# SH5_-_ARMCONTROLS.net
KiCad netlist of a schematic drawn in Altium Designer
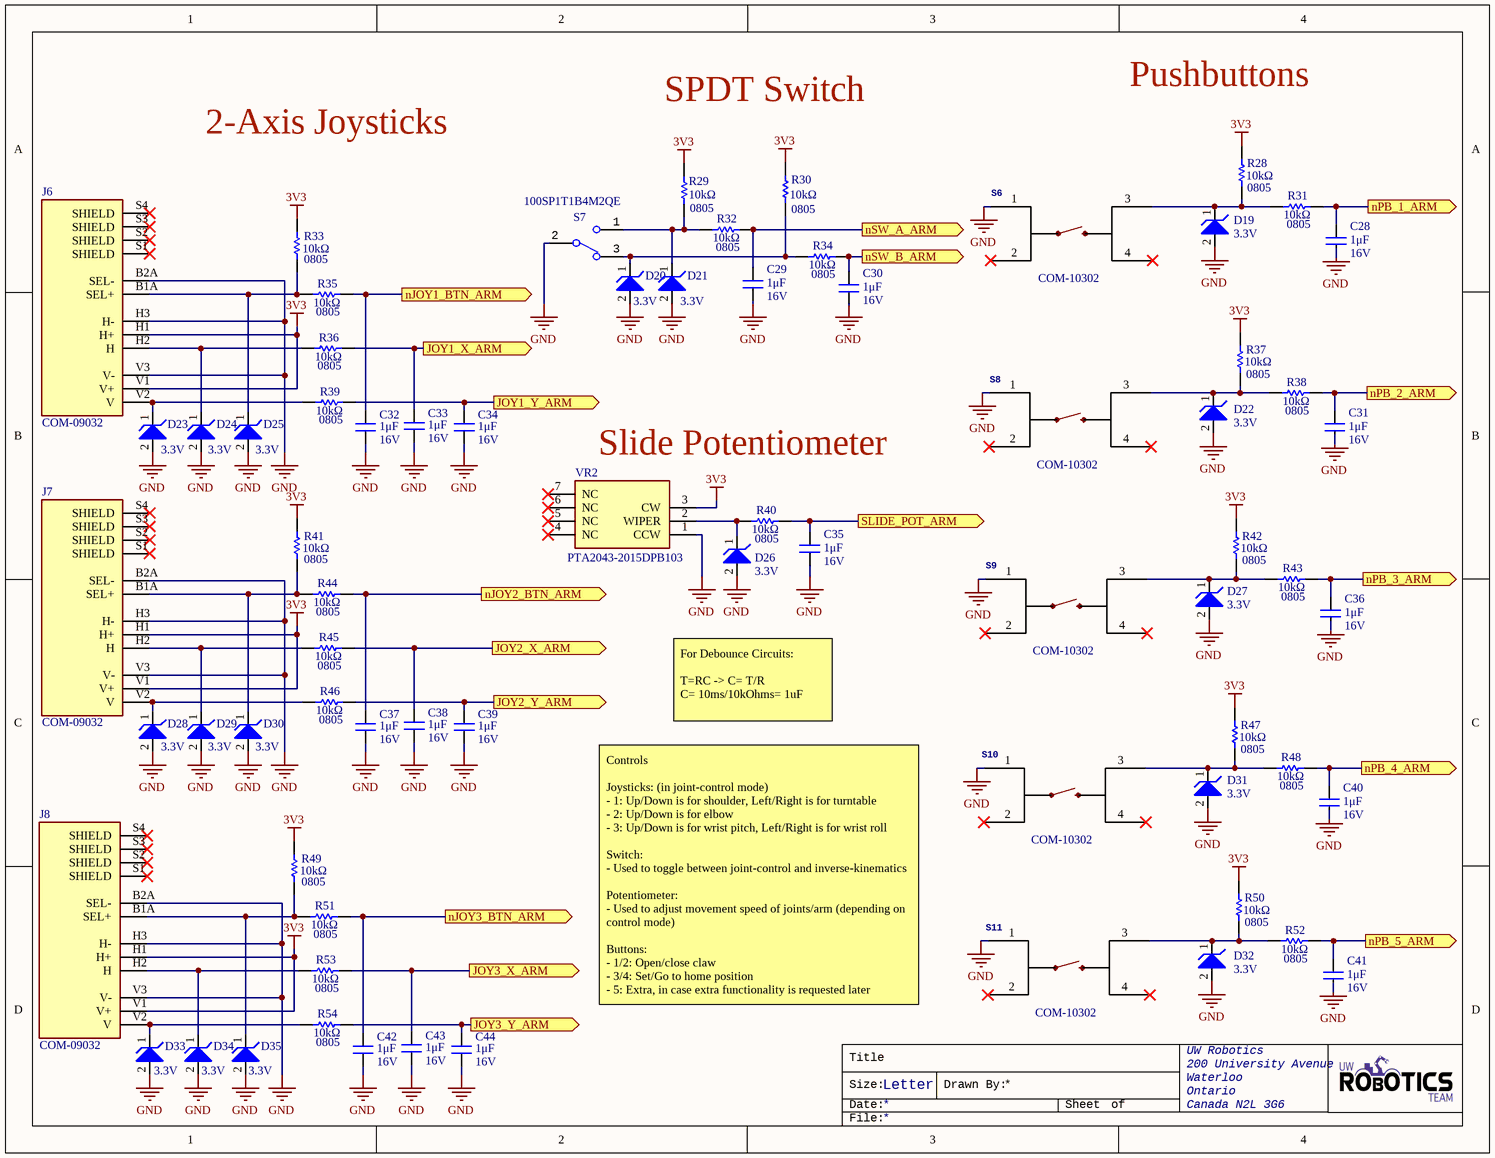
[diagram p0: SH5 - ARMCONTROLS.SchDoc]

(export (version "E")
  (design (tool "Eeschema 10.0.6"))
  (components
    (comp (ref "C28")
      (value "1μF")
      (footprint "CAP2012")
      (description "CAP CER 1UF 16V X7R 0805")
      (fields
        (field (name "TOLERANCE") "10%")
        (field (name "VOLTAGE RATING") "16V")
        (field (name "Comment") "CAP_1uF_16V_0805")
      )
      (libsource (lib "UWRT_Schematic_Library_2020") (part "CAP_1uF_16V_0805"))
    )
    (comp (ref "C29")
      (value "1μF")
      (footprint "CAP2012")
      (description "CAP CER 1UF 16V X7R 0805")
      (fields
        (field (name "TOLERANCE") "10%")
        (field (name "VOLTAGE RATING") "16V")
        (field (name "Comment") "CAP_1uF_16V_0805")
      )
      (libsource (lib "UWRT_Schematic_Library_2020") (part "CAP_1uF_16V_0805"))
    )
    (comp (ref "C30")
      (value "1μF")
      (footprint "CAP2012")
      (description "CAP CER 1UF 16V X7R 0805")
      (fields
        (field (name "TOLERANCE") "10%")
        (field (name "VOLTAGE RATING") "16V")
        (field (name "Comment") "CAP_1uF_16V_0805")
      )
      (libsource (lib "UWRT_Schematic_Library_2020") (part "CAP_1uF_16V_0805"))
    )
    (comp (ref "C31")
      (value "1μF")
      (footprint "CAP2012")
      (description "CAP CER 1UF 16V X7R 0805")
      (fields
        (field (name "TOLERANCE") "10%")
        (field (name "VOLTAGE RATING") "16V")
        (field (name "Comment") "CAP_1uF_16V_0805")
      )
      (libsource (lib "UWRT_Schematic_Library_2020") (part "CAP_1uF_16V_0805"))
    )
    (comp (ref "C32")
      (value "1μF")
      (footprint "CAP2012")
      (description "CAP CER 1UF 16V X7R 0805")
      (fields
        (field (name "TOLERANCE") "10%")
        (field (name "VOLTAGE RATING") "16V")
        (field (name "Comment") "CAP_1uF_16V_0805")
      )
      (libsource (lib "UWRT_Schematic_Library_2020") (part "CAP_1uF_16V_0805"))
    )
    (comp (ref "C33")
      (value "1μF")
      (footprint "CAP2012")
      (description "CAP CER 1UF 16V X7R 0805")
      (fields
        (field (name "TOLERANCE") "10%")
        (field (name "VOLTAGE RATING") "16V")
        (field (name "Comment") "CAP_1uF_16V_0805")
      )
      (libsource (lib "UWRT_Schematic_Library_2020") (part "CAP_1uF_16V_0805"))
    )
    (comp (ref "C34")
      (value "1μF")
      (footprint "CAP2012")
      (description "CAP CER 1UF 16V X7R 0805")
      (fields
        (field (name "TOLERANCE") "10%")
        (field (name "VOLTAGE RATING") "16V")
        (field (name "Comment") "CAP_1uF_16V_0805")
      )
      (libsource (lib "UWRT_Schematic_Library_2020") (part "CAP_1uF_16V_0805"))
    )
    (comp (ref "C35")
      (value "1μF")
      (footprint "CAP2012")
      (description "CAP CER 1UF 16V X7R 0805")
      (fields
        (field (name "TOLERANCE") "10%")
        (field (name "VOLTAGE RATING") "16V")
        (field (name "Comment") "CAP_1uF_16V_0805")
      )
      (libsource (lib "UWRT_Schematic_Library_2020") (part "CAP_1uF_16V_0805"))
    )
    (comp (ref "C36")
      (value "1μF")
      (footprint "CAP2012")
      (description "CAP CER 1UF 16V X7R 0805")
      (fields
        (field (name "TOLERANCE") "10%")
        (field (name "VOLTAGE RATING") "16V")
        (field (name "Comment") "CAP_1uF_16V_0805")
      )
      (libsource (lib "UWRT_Schematic_Library_2020") (part "CAP_1uF_16V_0805"))
    )
    (comp (ref "C37")
      (value "1μF")
      (footprint "CAP2012")
      (description "CAP CER 1UF 16V X7R 0805")
      (fields
        (field (name "TOLERANCE") "10%")
        (field (name "VOLTAGE RATING") "16V")
        (field (name "Comment") "CAP_1uF_16V_0805")
      )
      (libsource (lib "UWRT_Schematic_Library_2020") (part "CAP_1uF_16V_0805"))
    )
    (comp (ref "C38")
      (value "1μF")
      (footprint "CAP2012")
      (description "CAP CER 1UF 16V X7R 0805")
      (fields
        (field (name "TOLERANCE") "10%")
        (field (name "VOLTAGE RATING") "16V")
        (field (name "Comment") "CAP_1uF_16V_0805")
      )
      (libsource (lib "UWRT_Schematic_Library_2020") (part "CAP_1uF_16V_0805"))
    )
    (comp (ref "C39")
      (value "1μF")
      (footprint "CAP2012")
      (description "CAP CER 1UF 16V X7R 0805")
      (fields
        (field (name "TOLERANCE") "10%")
        (field (name "VOLTAGE RATING") "16V")
        (field (name "Comment") "CAP_1uF_16V_0805")
      )
      (libsource (lib "UWRT_Schematic_Library_2020") (part "CAP_1uF_16V_0805"))
    )
    (comp (ref "C40")
      (value "1μF")
      (footprint "CAP2012")
      (description "CAP CER 1UF 16V X7R 0805")
      (fields
        (field (name "TOLERANCE") "10%")
        (field (name "VOLTAGE RATING") "16V")
        (field (name "Comment") "CAP_1uF_16V_0805")
      )
      (libsource (lib "UWRT_Schematic_Library_2020") (part "CAP_1uF_16V_0805"))
    )
    (comp (ref "C41")
      (value "1μF")
      (footprint "CAP2012")
      (description "CAP CER 1UF 16V X7R 0805")
      (fields
        (field (name "TOLERANCE") "10%")
        (field (name "VOLTAGE RATING") "16V")
        (field (name "Comment") "CAP_1uF_16V_0805")
      )
      (libsource (lib "UWRT_Schematic_Library_2020") (part "CAP_1uF_16V_0805"))
    )
    (comp (ref "C42")
      (value "1μF")
      (footprint "CAP2012")
      (description "CAP CER 1UF 16V X7R 0805")
      (fields
        (field (name "TOLERANCE") "10%")
        (field (name "VOLTAGE RATING") "16V")
        (field (name "Comment") "CAP_1uF_16V_0805")
      )
      (libsource (lib "UWRT_Schematic_Library_2020") (part "CAP_1uF_16V_0805"))
    )
    (comp (ref "C43")
      (value "1μF")
      (footprint "CAP2012")
      (description "CAP CER 1UF 16V X7R 0805")
      (fields
        (field (name "TOLERANCE") "10%")
        (field (name "VOLTAGE RATING") "16V")
        (field (name "Comment") "CAP_1uF_16V_0805")
      )
      (libsource (lib "UWRT_Schematic_Library_2020") (part "CAP_1uF_16V_0805"))
    )
    (comp (ref "C44")
      (value "1μF")
      (footprint "CAP2012")
      (description "CAP CER 1UF 16V X7R 0805")
      (fields
        (field (name "TOLERANCE") "10%")
        (field (name "VOLTAGE RATING") "16V")
        (field (name "Comment") "CAP_1uF_16V_0805")
      )
      (libsource (lib "UWRT_Schematic_Library_2020") (part "CAP_1uF_16V_0805"))
    )
    (comp (ref "D19")
      (value "TVS_DIODE_UNIDIR_3.3V")
      (footprint "SOD523")
      (description "TVS DIODE 3.3V 14.1V SOD523. Used to protect each connector input line going into the MCU.")
      (fields (field (name "REVERSE STANDOFF VOLTAGE") "3.3V"))
      (libsource (lib "UWRT_Schematic_Library_2020") (part "TVS_DIODE_UNIDIR_3.3V"))
    )
    (comp (ref "D20")
      (value "TVS_DIODE_UNIDIR_3.3V")
      (footprint "SOD523")
      (description "TVS DIODE 3.3V 14.1V SOD523. Used to protect each connector input line going into the MCU.")
      (fields (field (name "REVERSE STANDOFF VOLTAGE") "3.3V"))
      (libsource (lib "UWRT_Schematic_Library_2020") (part "TVS_DIODE_UNIDIR_3.3V"))
    )
    (comp (ref "D21")
      (value "TVS_DIODE_UNIDIR_3.3V")
      (footprint "SOD523")
      (description "TVS DIODE 3.3V 14.1V SOD523. Used to protect each connector input line going into the MCU.")
      (fields (field (name "REVERSE STANDOFF VOLTAGE") "3.3V"))
      (libsource (lib "UWRT_Schematic_Library_2020") (part "TVS_DIODE_UNIDIR_3.3V"))
    )
    (comp (ref "D22")
      (value "TVS_DIODE_UNIDIR_3.3V")
      (footprint "SOD523")
      (description "TVS DIODE 3.3V 14.1V SOD523. Used to protect each connector input line going into the MCU.")
      (fields (field (name "REVERSE STANDOFF VOLTAGE") "3.3V"))
      (libsource (lib "UWRT_Schematic_Library_2020") (part "TVS_DIODE_UNIDIR_3.3V"))
    )
    (comp (ref "D23")
      (value "TVS_DIODE_UNIDIR_3.3V")
      (footprint "SOD523")
      (description "TVS DIODE 3.3V 14.1V SOD523. Used to protect each connector input line going into the MCU.")
      (fields (field (name "REVERSE STANDOFF VOLTAGE") "3.3V"))
      (libsource (lib "UWRT_Schematic_Library_2020") (part "TVS_DIODE_UNIDIR_3.3V"))
    )
    (comp (ref "D24")
      (value "TVS_DIODE_UNIDIR_3.3V")
      (footprint "SOD523")
      (description "TVS DIODE 3.3V 14.1V SOD523. Used to protect each connector input line going into the MCU.")
      (fields (field (name "REVERSE STANDOFF VOLTAGE") "3.3V"))
      (libsource (lib "UWRT_Schematic_Library_2020") (part "TVS_DIODE_UNIDIR_3.3V"))
    )
    (comp (ref "D25")
      (value "TVS_DIODE_UNIDIR_3.3V")
      (footprint "SOD523")
      (description "TVS DIODE 3.3V 14.1V SOD523. Used to protect each connector input line going into the MCU.")
      (fields (field (name "REVERSE STANDOFF VOLTAGE") "3.3V"))
      (libsource (lib "UWRT_Schematic_Library_2020") (part "TVS_DIODE_UNIDIR_3.3V"))
    )
    (comp (ref "D26")
      (value "TVS_DIODE_UNIDIR_3.3V")
      (footprint "SOD523")
      (description "TVS DIODE 3.3V 14.1V SOD523. Used to protect each connector input line going into the MCU.")
      (fields (field (name "REVERSE STANDOFF VOLTAGE") "3.3V"))
      (libsource (lib "UWRT_Schematic_Library_2020") (part "TVS_DIODE_UNIDIR_3.3V"))
    )
    (comp (ref "D27")
      (value "TVS_DIODE_UNIDIR_3.3V")
      (footprint "SOD523")
      (description "TVS DIODE 3.3V 14.1V SOD523. Used to protect each connector input line going into the MCU.")
      (fields (field (name "REVERSE STANDOFF VOLTAGE") "3.3V"))
      (libsource (lib "UWRT_Schematic_Library_2020") (part "TVS_DIODE_UNIDIR_3.3V"))
    )
    (comp (ref "D28")
      (value "TVS_DIODE_UNIDIR_3.3V")
      (footprint "SOD523")
      (description "TVS DIODE 3.3V 14.1V SOD523. Used to protect each connector input line going into the MCU.")
      (fields (field (name "REVERSE STANDOFF VOLTAGE") "3.3V"))
      (libsource (lib "UWRT_Schematic_Library_2020") (part "TVS_DIODE_UNIDIR_3.3V"))
    )
    (comp (ref "D29")
      (value "TVS_DIODE_UNIDIR_3.3V")
      (footprint "SOD523")
      (description "TVS DIODE 3.3V 14.1V SOD523. Used to protect each connector input line going into the MCU.")
      (fields (field (name "REVERSE STANDOFF VOLTAGE") "3.3V"))
      (libsource (lib "UWRT_Schematic_Library_2020") (part "TVS_DIODE_UNIDIR_3.3V"))
    )
    (comp (ref "D30")
      (value "TVS_DIODE_UNIDIR_3.3V")
      (footprint "SOD523")
      (description "TVS DIODE 3.3V 14.1V SOD523. Used to protect each connector input line going into the MCU.")
      (fields (field (name "REVERSE STANDOFF VOLTAGE") "3.3V"))
      (libsource (lib "UWRT_Schematic_Library_2020") (part "TVS_DIODE_UNIDIR_3.3V"))
    )
    (comp (ref "D31")
      (value "TVS_DIODE_UNIDIR_3.3V")
      (footprint "SOD523")
      (description "TVS DIODE 3.3V 14.1V SOD523. Used to protect each connector input line going into the MCU.")
      (fields (field (name "REVERSE STANDOFF VOLTAGE") "3.3V"))
      (libsource (lib "UWRT_Schematic_Library_2020") (part "TVS_DIODE_UNIDIR_3.3V"))
    )
    (comp (ref "D32")
      (value "TVS_DIODE_UNIDIR_3.3V")
      (footprint "SOD523")
      (description "TVS DIODE 3.3V 14.1V SOD523. Used to protect each connector input line going into the MCU.")
      (fields (field (name "REVERSE STANDOFF VOLTAGE") "3.3V"))
      (libsource (lib "UWRT_Schematic_Library_2020") (part "TVS_DIODE_UNIDIR_3.3V"))
    )
    (comp (ref "D33")
      (value "TVS_DIODE_UNIDIR_3.3V")
      (footprint "SOD523")
      (description "TVS DIODE 3.3V 14.1V SOD523. Used to protect each connector input line going into the MCU.")
      (fields (field (name "REVERSE STANDOFF VOLTAGE") "3.3V"))
      (libsource (lib "UWRT_Schematic_Library_2020") (part "TVS_DIODE_UNIDIR_3.3V"))
    )
    (comp (ref "D34")
      (value "TVS_DIODE_UNIDIR_3.3V")
      (footprint "SOD523")
      (description "TVS DIODE 3.3V 14.1V SOD523. Used to protect each connector input line going into the MCU.")
      (fields (field (name "REVERSE STANDOFF VOLTAGE") "3.3V"))
      (libsource (lib "UWRT_Schematic_Library_2020") (part "TVS_DIODE_UNIDIR_3.3V"))
    )
    (comp (ref "D35")
      (value "TVS_DIODE_UNIDIR_3.3V")
      (footprint "SOD523")
      (description "TVS DIODE 3.3V 14.1V SOD523. Used to protect each connector input line going into the MCU.")
      (fields (field (name "REVERSE STANDOFF VOLTAGE") "3.3V"))
      (libsource (lib "UWRT_Schematic_Library_2020") (part "TVS_DIODE_UNIDIR_3.3V"))
    )
    (comp (ref "J6")
      (value "2_AXIS_JOYSTICK")
      (footprint "2_AXIS_JOYSTICK")
      (description "JOYSTICK 10K OHM 2 AXIS TH")
      (fields (field (name "MANUFACTURER PART NUMBER 1") "COM-09032"))
      (libsource (lib "UWRT_Schematic_Library_2020") (part "2_AXIS_JOYSTICK"))
    )
    (comp (ref "J7")
      (value "2_AXIS_JOYSTICK")
      (footprint "2_AXIS_JOYSTICK")
      (description "JOYSTICK 10K OHM 2 AXIS TH")
      (fields (field (name "MANUFACTURER PART NUMBER 1") "COM-09032"))
      (libsource (lib "UWRT_Schematic_Library_2020") (part "2_AXIS_JOYSTICK"))
    )
    (comp (ref "J8")
      (value "2_AXIS_JOYSTICK")
      (footprint "2_AXIS_JOYSTICK")
      (description "JOYSTICK 10K OHM 2 AXIS TH")
      (fields (field (name "MANUFACTURER PART NUMBER 1") "COM-09032"))
      (libsource (lib "UWRT_Schematic_Library_2020") (part "2_AXIS_JOYSTICK"))
    )
    (comp (ref "R28")
      (value "10kΩ")
      (footprint "RESC0805")
      (description "RES 10K OHM 5% 1/8W 0805")
      (fields (field (name "CASE CODE (IMPERIAL)") "0805") (field (name "Comment") "RES_10kΩ_0805_5%"))
      (libsource (lib "UWRT_Schematic_Library_2020") (part "RES_10kΩ_0805_5%"))
    )
    (comp (ref "R29")
      (value "10kΩ")
      (footprint "RESC0805")
      (description "RES 10K OHM 5% 1/8W 0805")
      (fields (field (name "CASE CODE (IMPERIAL)") "0805") (field (name "Comment") "RES_10kΩ_0805_5%"))
      (libsource (lib "UWRT_Schematic_Library_2020") (part "RES_10kΩ_0805_5%"))
    )
    (comp (ref "R30")
      (value "10kΩ")
      (footprint "RESC0805")
      (description "RES 10K OHM 5% 1/8W 0805")
      (fields (field (name "CASE CODE (IMPERIAL)") "0805") (field (name "Comment") "RES_10kΩ_0805_5%"))
      (libsource (lib "UWRT_Schematic_Library_2020") (part "RES_10kΩ_0805_5%"))
    )
    (comp (ref "R31")
      (value "10kΩ")
      (footprint "RESC0805")
      (description "RES 10K OHM 5% 1/8W 0805")
      (fields (field (name "CASE CODE (IMPERIAL)") "0805") (field (name "Comment") "RES_10kΩ_0805_5%"))
      (libsource (lib "UWRT_Schematic_Library_2020") (part "RES_10kΩ_0805_5%"))
    )
    (comp (ref "R32")
      (value "10kΩ")
      (footprint "RESC0805")
      (description "RES 10K OHM 5% 1/8W 0805")
      (fields (field (name "CASE CODE (IMPERIAL)") "0805") (field (name "Comment") "RES_10kΩ_0805_5%"))
      (libsource (lib "UWRT_Schematic_Library_2020") (part "RES_10kΩ_0805_5%"))
    )
    (comp (ref "R33")
      (value "10kΩ")
      (footprint "RESC0805")
      (description "RES 10K OHM 5% 1/8W 0805")
      (fields (field (name "CASE CODE (IMPERIAL)") "0805") (field (name "Comment") "RES_10kΩ_0805_5%"))
      (libsource (lib "UWRT_Schematic_Library_2020") (part "RES_10kΩ_0805_5%"))
    )
    (comp (ref "R34")
      (value "10kΩ")
      (footprint "RESC0805")
      (description "RES 10K OHM 5% 1/8W 0805")
      (fields (field (name "CASE CODE (IMPERIAL)") "0805") (field (name "Comment") "RES_10kΩ_0805_5%"))
      (libsource (lib "UWRT_Schematic_Library_2020") (part "RES_10kΩ_0805_5%"))
    )
    (comp (ref "R35")
      (value "10kΩ")
      (footprint "RESC0805")
      (description "RES 10K OHM 5% 1/8W 0805")
      (fields (field (name "CASE CODE (IMPERIAL)") "0805") (field (name "Comment") "RES_10kΩ_0805_5%"))
      (libsource (lib "UWRT_Schematic_Library_2020") (part "RES_10kΩ_0805_5%"))
    )
    (comp (ref "R36")
      (value "10kΩ")
      (footprint "RESC0805")
      (description "RES 10K OHM 5% 1/8W 0805")
      (fields (field (name "CASE CODE (IMPERIAL)") "0805") (field (name "Comment") "RES_10kΩ_0805_5%"))
      (libsource (lib "UWRT_Schematic_Library_2020") (part "RES_10kΩ_0805_5%"))
    )
    (comp (ref "R37")
      (value "10kΩ")
      (footprint "RESC0805")
      (description "RES 10K OHM 5% 1/8W 0805")
      (fields (field (name "CASE CODE (IMPERIAL)") "0805") (field (name "Comment") "RES_10kΩ_0805_5%"))
      (libsource (lib "UWRT_Schematic_Library_2020") (part "RES_10kΩ_0805_5%"))
    )
    (comp (ref "R38")
      (value "10kΩ")
      (footprint "RESC0805")
      (description "RES 10K OHM 5% 1/8W 0805")
      (fields (field (name "CASE CODE (IMPERIAL)") "0805") (field (name "Comment") "RES_10kΩ_0805_5%"))
      (libsource (lib "UWRT_Schematic_Library_2020") (part "RES_10kΩ_0805_5%"))
    )
    (comp (ref "R39")
      (value "10kΩ")
      (footprint "RESC0805")
      (description "RES 10K OHM 5% 1/8W 0805")
      (fields (field (name "CASE CODE (IMPERIAL)") "0805") (field (name "Comment") "RES_10kΩ_0805_5%"))
      (libsource (lib "UWRT_Schematic_Library_2020") (part "RES_10kΩ_0805_5%"))
    )
    (comp (ref "R40")
      (value "10kΩ")
      (footprint "RESC0805")
      (description "RES 10K OHM 5% 1/8W 0805")
      (fields (field (name "CASE CODE (IMPERIAL)") "0805") (field (name "Comment") "RES_10kΩ_0805_5%"))
      (libsource (lib "UWRT_Schematic_Library_2020") (part "RES_10kΩ_0805_5%"))
    )
    (comp (ref "R41")
      (value "10kΩ")
      (footprint "RESC0805")
      (description "RES 10K OHM 5% 1/8W 0805")
      (fields (field (name "CASE CODE (IMPERIAL)") "0805") (field (name "Comment") "RES_10kΩ_0805_5%"))
      (libsource (lib "UWRT_Schematic_Library_2020") (part "RES_10kΩ_0805_5%"))
    )
    (comp (ref "R42")
      (value "10kΩ")
      (footprint "RESC0805")
      (description "RES 10K OHM 5% 1/8W 0805")
      (fields (field (name "CASE CODE (IMPERIAL)") "0805") (field (name "Comment") "RES_10kΩ_0805_5%"))
      (libsource (lib "UWRT_Schematic_Library_2020") (part "RES_10kΩ_0805_5%"))
    )
    (comp (ref "R43")
      (value "10kΩ")
      (footprint "RESC0805")
      (description "RES 10K OHM 5% 1/8W 0805")
      (fields (field (name "CASE CODE (IMPERIAL)") "0805") (field (name "Comment") "RES_10kΩ_0805_5%"))
      (libsource (lib "UWRT_Schematic_Library_2020") (part "RES_10kΩ_0805_5%"))
    )
    (comp (ref "R44")
      (value "10kΩ")
      (footprint "RESC0805")
      (description "RES 10K OHM 5% 1/8W 0805")
      (fields (field (name "CASE CODE (IMPERIAL)") "0805") (field (name "Comment") "RES_10kΩ_0805_5%"))
      (libsource (lib "UWRT_Schematic_Library_2020") (part "RES_10kΩ_0805_5%"))
    )
    (comp (ref "R45")
      (value "10kΩ")
      (footprint "RESC0805")
      (description "RES 10K OHM 5% 1/8W 0805")
      (fields (field (name "CASE CODE (IMPERIAL)") "0805") (field (name "Comment") "RES_10kΩ_0805_5%"))
      (libsource (lib "UWRT_Schematic_Library_2020") (part "RES_10kΩ_0805_5%"))
    )
    (comp (ref "R46")
      (value "10kΩ")
      (footprint "RESC0805")
      (description "RES 10K OHM 5% 1/8W 0805")
      (fields (field (name "CASE CODE (IMPERIAL)") "0805") (field (name "Comment") "RES_10kΩ_0805_5%"))
      (libsource (lib "UWRT_Schematic_Library_2020") (part "RES_10kΩ_0805_5%"))
    )
    (comp (ref "R47")
      (value "10kΩ")
      (footprint "RESC0805")
      (description "RES 10K OHM 5% 1/8W 0805")
      (fields (field (name "CASE CODE (IMPERIAL)") "0805") (field (name "Comment") "RES_10kΩ_0805_5%"))
      (libsource (lib "UWRT_Schematic_Library_2020") (part "RES_10kΩ_0805_5%"))
    )
    (comp (ref "R48")
      (value "10kΩ")
      (footprint "RESC0805")
      (description "RES 10K OHM 5% 1/8W 0805")
      (fields (field (name "CASE CODE (IMPERIAL)") "0805") (field (name "Comment") "RES_10kΩ_0805_5%"))
      (libsource (lib "UWRT_Schematic_Library_2020") (part "RES_10kΩ_0805_5%"))
    )
    (comp (ref "R49")
      (value "10kΩ")
      (footprint "RESC0805")
      (description "RES 10K OHM 5% 1/8W 0805")
      (fields (field (name "CASE CODE (IMPERIAL)") "0805") (field (name "Comment") "RES_10kΩ_0805_5%"))
      (libsource (lib "UWRT_Schematic_Library_2020") (part "RES_10kΩ_0805_5%"))
    )
    (comp (ref "R50")
      (value "10kΩ")
      (footprint "RESC0805")
      (description "RES 10K OHM 5% 1/8W 0805")
      (fields (field (name "CASE CODE (IMPERIAL)") "0805") (field (name "Comment") "RES_10kΩ_0805_5%"))
      (libsource (lib "UWRT_Schematic_Library_2020") (part "RES_10kΩ_0805_5%"))
    )
    (comp (ref "R51")
      (value "10kΩ")
      (footprint "RESC0805")
      (description "RES 10K OHM 5% 1/8W 0805")
      (fields (field (name "CASE CODE (IMPERIAL)") "0805") (field (name "Comment") "RES_10kΩ_0805_5%"))
      (libsource (lib "UWRT_Schematic_Library_2020") (part "RES_10kΩ_0805_5%"))
    )
    (comp (ref "R52")
      (value "10kΩ")
      (footprint "RESC0805")
      (description "RES 10K OHM 5% 1/8W 0805")
      (fields (field (name "CASE CODE (IMPERIAL)") "0805") (field (name "Comment") "RES_10kΩ_0805_5%"))
      (libsource (lib "UWRT_Schematic_Library_2020") (part "RES_10kΩ_0805_5%"))
    )
    (comp (ref "R53")
      (value "10kΩ")
      (footprint "RESC0805")
      (description "RES 10K OHM 5% 1/8W 0805")
      (fields (field (name "CASE CODE (IMPERIAL)") "0805") (field (name "Comment") "RES_10kΩ_0805_5%"))
      (libsource (lib "UWRT_Schematic_Library_2020") (part "RES_10kΩ_0805_5%"))
    )
    (comp (ref "R54")
      (value "10kΩ")
      (footprint "RESC0805")
      (description "RES 10K OHM 5% 1/8W 0805")
      (fields (field (name "CASE CODE (IMPERIAL)") "0805") (field (name "Comment") "RES_10kΩ_0805_5%"))
      (libsource (lib "UWRT_Schematic_Library_2020") (part "RES_10kΩ_0805_5%"))
    )
    (comp (ref "S6")
      (value "Pushbutton")
      (footprint "TACTILE_SWITCH_PTH_12MM")
      (description "TACTILE MOMENTARY PUSHBUTTON SPST")
      (fields (field (name "MANUFACTURER PART NUMBER 1") "COM-10302"))
      (libsource (lib "UWRT_Schematic_Library_2020") (part "MOMENTARY_SWITCH_TH"))
    )
    (comp (ref "S7")
      (value "100SP1T1B4M2QE")
      (footprint "100SP1T1B4M2QE")
      (description "SWITCH TOGGLE SPDT 5A 120V")
      (fields (field (name "MANUFACTURER PART NUMBER 1") "100SP1T1B4M2QE"))
      (libsource (lib "UWRT_Schematic_Library_2020") (part "SW_SPDT"))
    )
    (comp (ref "S8")
      (value "Pushbutton")
      (footprint "TACTILE_SWITCH_PTH_12MM")
      (description "TACTILE MOMENTARY PUSHBUTTON SPST")
      (fields (field (name "MANUFACTURER PART NUMBER 1") "COM-10302"))
      (libsource (lib "UWRT_Schematic_Library_2020") (part "MOMENTARY_SWITCH_TH"))
    )
    (comp (ref "S9")
      (value "Pushbutton")
      (footprint "TACTILE_SWITCH_PTH_12MM")
      (description "TACTILE MOMENTARY PUSHBUTTON SPST")
      (fields (field (name "MANUFACTURER PART NUMBER 1") "COM-10302"))
      (libsource (lib "UWRT_Schematic_Library_2020") (part "MOMENTARY_SWITCH_TH"))
    )
    (comp (ref "S10")
      (value "Pushbutton")
      (footprint "TACTILE_SWITCH_PTH_12MM")
      (description "TACTILE MOMENTARY PUSHBUTTON SPST")
      (fields (field (name "MANUFACTURER PART NUMBER 1") "COM-10302"))
      (libsource (lib "UWRT_Schematic_Library_2020") (part "MOMENTARY_SWITCH_TH"))
    )
    (comp (ref "S11")
      (value "Pushbutton")
      (footprint "TACTILE_SWITCH_PTH_12MM")
      (description "TACTILE MOMENTARY PUSHBUTTON SPST")
      (fields (field (name "MANUFACTURER PART NUMBER 1") "COM-10302"))
      (libsource (lib "UWRT_Schematic_Library_2020") (part "MOMENTARY_SWITCH_TH"))
    )
    (comp (ref "VR2")
      (value "POT_10K_SLIDE")
      (footprint "PTA20432015CPB103")
      (description "SLIDE POT 10K OHM 0.1W TOP 20MM")
      (fields
        (field (name "MANUFACTURER PART NUMBER 1") "PTA2043-2015DPB103")
        (field (name "TOLERANCE") "20%")
      )
      (libsource (lib "UWRT_Schematic_Library_2020") (part "POT_10K_SLIDE"))
    )
  )
  (nets
    (net (code "1") (name "/JOY1_X_ARM") (class "Default")
      (node (ref "C33") (pin "2") (pinfunction "2_2") (pintype "passive"))
      (node (ref "R36") (pin "2") (pinfunction "2_2") (pintype "passive"))
    )
    (net (code "2") (name "/JOY1_Y_ARM") (class "Default")
      (node (ref "C34") (pin "2") (pinfunction "2_2") (pintype "passive"))
      (node (ref "R39") (pin "2") (pinfunction "2_2") (pintype "passive"))
    )
    (net (code "3") (name "/JOY2_X_ARM") (class "Default")
      (node (ref "C38") (pin "2") (pinfunction "2_2") (pintype "passive"))
      (node (ref "R45") (pin "2") (pinfunction "2_2") (pintype "passive"))
    )
    (net (code "4") (name "/JOY2_Y_ARM") (class "Default")
      (node (ref "C39") (pin "2") (pinfunction "2_2") (pintype "passive"))
      (node (ref "R46") (pin "2") (pinfunction "2_2") (pintype "passive"))
    )
    (net (code "5") (name "/JOY3_X_ARM") (class "Default")
      (node (ref "C43") (pin "2") (pinfunction "2_2") (pintype "passive"))
      (node (ref "R53") (pin "2") (pinfunction "2_2") (pintype "passive"))
    )
    (net (code "6") (name "/JOY3_Y_ARM") (class "Default")
      (node (ref "C44") (pin "2") (pinfunction "2_2") (pintype "passive"))
      (node (ref "R54") (pin "2") (pinfunction "2_2") (pintype "passive"))
    )
    (net (code "7") (name "/SLIDE_POT_ARM") (class "Default")
      (node (ref "C35") (pin "2") (pinfunction "2_2") (pintype "passive"))
      (node (ref "R40") (pin "2") (pinfunction "2_2") (pintype "passive"))
    )
    (net (code "8") (name "/nJOY1_BTN_ARM") (class "Default")
      (node (ref "C32") (pin "2") (pinfunction "2_2") (pintype "passive"))
      (node (ref "R35") (pin "2") (pinfunction "2_2") (pintype "passive"))
    )
    (net (code "9") (name "/nJOY2_BTN_ARM") (class "Default")
      (node (ref "C37") (pin "2") (pinfunction "2_2") (pintype "passive"))
      (node (ref "R44") (pin "2") (pinfunction "2_2") (pintype "passive"))
    )
    (net (code "10") (name "/nJOY3_BTN_ARM") (class "Default")
      (node (ref "C42") (pin "2") (pinfunction "2_2") (pintype "passive"))
      (node (ref "R51") (pin "2") (pinfunction "2_2") (pintype "passive"))
    )
    (net (code "11") (name "/nPB_1_ARM") (class "Default")
      (node (ref "C28") (pin "2") (pinfunction "2_2") (pintype "passive"))
      (node (ref "R31") (pin "2") (pinfunction "2_2") (pintype "passive"))
    )
    (net (code "12") (name "/nPB_2_ARM") (class "Default")
      (node (ref "C31") (pin "2") (pinfunction "2_2") (pintype "passive"))
      (node (ref "R38") (pin "2") (pinfunction "2_2") (pintype "passive"))
    )
    (net (code "13") (name "/nPB_3_ARM") (class "Default")
      (node (ref "C36") (pin "2") (pinfunction "2_2") (pintype "passive"))
      (node (ref "R43") (pin "2") (pinfunction "2_2") (pintype "passive"))
    )
    (net (code "14") (name "/nPB_4_ARM") (class "Default")
      (node (ref "C40") (pin "2") (pinfunction "2_2") (pintype "passive"))
      (node (ref "R48") (pin "2") (pinfunction "2_2") (pintype "passive"))
    )
    (net (code "15") (name "/nPB_5_ARM") (class "Default")
      (node (ref "C41") (pin "2") (pinfunction "2_2") (pintype "passive"))
      (node (ref "R52") (pin "2") (pinfunction "2_2") (pintype "passive"))
    )
    (net (code "16") (name "/nSW_A_ARM") (class "Default")
      (node (ref "C29") (pin "2") (pinfunction "2_2") (pintype "passive"))
      (node (ref "R32") (pin "2") (pinfunction "2_2") (pintype "passive"))
    )
    (net (code "17") (name "/nSW_B_ARM") (class "Default")
      (node (ref "C30") (pin "2") (pinfunction "2_2") (pintype "passive"))
      (node (ref "R34") (pin "2") (pinfunction "2_2") (pintype "passive"))
    )
    (net (code "18") (name "3V3") (class "Default")
      (node (ref "J6") (pin "H1") (pinfunction "H+_H1") (pintype "passive"))
      (node (ref "J6") (pin "V1") (pinfunction "V+_V1") (pintype "passive"))
      (node (ref "J7") (pin "H1") (pinfunction "H+_H1") (pintype "passive"))
      (node (ref "J7") (pin "V1") (pinfunction "V+_V1") (pintype "passive"))
      (node (ref "J8") (pin "H1") (pinfunction "H+_H1") (pintype "passive"))
      (node (ref "J8") (pin "V1") (pinfunction "V+_V1") (pintype "passive"))
      (node (ref "R28") (pin "1") (pinfunction "1_1") (pintype "passive"))
      (node (ref "R29") (pin "1") (pinfunction "1_1") (pintype "passive"))
      (node (ref "R30") (pin "1") (pinfunction "1_1") (pintype "passive"))
      (node (ref "R33") (pin "1") (pinfunction "1_1") (pintype "passive"))
      (node (ref "R37") (pin "1") (pinfunction "1_1") (pintype "passive"))
      (node (ref "R41") (pin "1") (pinfunction "1_1") (pintype "passive"))
      (node (ref "R42") (pin "1") (pinfunction "1_1") (pintype "passive"))
      (node (ref "R47") (pin "1") (pinfunction "1_1") (pintype "passive"))
      (node (ref "R49") (pin "1") (pinfunction "1_1") (pintype "passive"))
      (node (ref "R50") (pin "1") (pinfunction "1_1") (pintype "passive"))
      (node (ref "VR2") (pin "3") (pinfunction "CW_3") (pintype "passive"))
    )
    (net (code "19") (name "GND") (class "Default")
      (node (ref "C28") (pin "1") (pinfunction "1_1") (pintype "passive"))
      (node (ref "C29") (pin "1") (pinfunction "1_1") (pintype "passive"))
      (node (ref "C30") (pin "1") (pinfunction "1_1") (pintype "passive"))
      (node (ref "C31") (pin "1") (pinfunction "1_1") (pintype "passive"))
      (node (ref "C32") (pin "1") (pinfunction "1_1") (pintype "passive"))
      (node (ref "C33") (pin "1") (pinfunction "1_1") (pintype "passive"))
      (node (ref "C34") (pin "1") (pinfunction "1_1") (pintype "passive"))
      (node (ref "C35") (pin "1") (pinfunction "1_1") (pintype "passive"))
      (node (ref "C36") (pin "1") (pinfunction "1_1") (pintype "passive"))
      (node (ref "C37") (pin "1") (pinfunction "1_1") (pintype "passive"))
      (node (ref "C38") (pin "1") (pinfunction "1_1") (pintype "passive"))
      (node (ref "C39") (pin "1") (pinfunction "1_1") (pintype "passive"))
      (node (ref "C40") (pin "1") (pinfunction "1_1") (pintype "passive"))
      (node (ref "C41") (pin "1") (pinfunction "1_1") (pintype "passive"))
      (node (ref "C42") (pin "1") (pinfunction "1_1") (pintype "passive"))
      (node (ref "C43") (pin "1") (pinfunction "1_1") (pintype "passive"))
      (node (ref "C44") (pin "1") (pinfunction "1_1") (pintype "passive"))
      (node (ref "D19") (pin "2") (pinfunction "2_2") (pintype "passive"))
      (node (ref "D20") (pin "2") (pinfunction "2_2") (pintype "passive"))
      (node (ref "D21") (pin "2") (pinfunction "2_2") (pintype "passive"))
      (node (ref "D22") (pin "2") (pinfunction "2_2") (pintype "passive"))
      (node (ref "D23") (pin "2") (pinfunction "2_2") (pintype "passive"))
      (node (ref "D24") (pin "2") (pinfunction "2_2") (pintype "passive"))
      (node (ref "D25") (pin "2") (pinfunction "2_2") (pintype "passive"))
      (node (ref "D26") (pin "2") (pinfunction "2_2") (pintype "passive"))
      (node (ref "D27") (pin "2") (pinfunction "2_2") (pintype "passive"))
      (node (ref "D28") (pin "2") (pinfunction "2_2") (pintype "passive"))
      (node (ref "D29") (pin "2") (pinfunction "2_2") (pintype "passive"))
      (node (ref "D30") (pin "2") (pinfunction "2_2") (pintype "passive"))
      (node (ref "D31") (pin "2") (pinfunction "2_2") (pintype "passive"))
      (node (ref "D32") (pin "2") (pinfunction "2_2") (pintype "passive"))
      (node (ref "D33") (pin "2") (pinfunction "2_2") (pintype "passive"))
      (node (ref "D34") (pin "2") (pinfunction "2_2") (pintype "passive"))
      (node (ref "D35") (pin "2") (pinfunction "2_2") (pintype "passive"))
      (node (ref "J6") (pin "B2A") (pinfunction "SEL-_B2A") (pintype "passive"))
      (node (ref "J6") (pin "H3") (pinfunction "H-_H3") (pintype "passive"))
      (node (ref "J6") (pin "V3") (pinfunction "V-_V3") (pintype "passive"))
      (node (ref "J7") (pin "B2A") (pinfunction "SEL-_B2A") (pintype "passive"))
      (node (ref "J7") (pin "H3") (pinfunction "H-_H3") (pintype "passive"))
      (node (ref "J7") (pin "V3") (pinfunction "V-_V3") (pintype "passive"))
      (node (ref "J8") (pin "B2A") (pinfunction "SEL-_B2A") (pintype "passive"))
      (node (ref "J8") (pin "H3") (pinfunction "H-_H3") (pintype "passive"))
      (node (ref "J8") (pin "V3") (pinfunction "V-_V3") (pintype "passive"))
      (node (ref "S10") (pin "1") (pinfunction "1_1") (pintype "passive"))
      (node (ref "S11") (pin "1") (pinfunction "1_1") (pintype "passive"))
      (node (ref "S6") (pin "1") (pinfunction "1_1") (pintype "passive"))
      (node (ref "S7") (pin "2") (pinfunction "2_2") (pintype "passive"))
      (node (ref "S8") (pin "1") (pinfunction "1_1") (pintype "passive"))
      (node (ref "S9") (pin "1") (pinfunction "1_1") (pintype "passive"))
      (node (ref "VR2") (pin "1") (pinfunction "CCW_1") (pintype "passive"))
    )
    (net (code "20") (name "Net-(D19-Pad1)") (class "Default")
      (node (ref "D19") (pin "1") (pinfunction "1_1") (pintype "passive"))
      (node (ref "R28") (pin "2") (pinfunction "2_2") (pintype "passive"))
      (node (ref "R31") (pin "1") (pinfunction "1_1") (pintype "passive"))
      (node (ref "S6") (pin "3") (pinfunction "3_3") (pintype "passive"))
    )
    (net (code "21") (name "Net-(D20-Pad1)") (class "Default")
      (node (ref "D20") (pin "1") (pinfunction "1_1") (pintype "passive"))
      (node (ref "R30") (pin "2") (pinfunction "2_2") (pintype "passive"))
      (node (ref "R34") (pin "1") (pinfunction "1_1") (pintype "passive"))
      (node (ref "S7") (pin "3") (pinfunction "3_3") (pintype "passive"))
    )
    (net (code "22") (name "Net-(D21-Pad1)") (class "Default")
      (node (ref "D21") (pin "1") (pinfunction "1_1") (pintype "passive"))
      (node (ref "R29") (pin "2") (pinfunction "2_2") (pintype "passive"))
      (node (ref "R32") (pin "1") (pinfunction "1_1") (pintype "passive"))
      (node (ref "S7") (pin "1") (pinfunction "1_1") (pintype "passive"))
    )
    (net (code "23") (name "Net-(D22-Pad1)") (class "Default")
      (node (ref "D22") (pin "1") (pinfunction "1_1") (pintype "passive"))
      (node (ref "R37") (pin "2") (pinfunction "2_2") (pintype "passive"))
      (node (ref "R38") (pin "1") (pinfunction "1_1") (pintype "passive"))
      (node (ref "S8") (pin "3") (pinfunction "3_3") (pintype "passive"))
    )
    (net (code "24") (name "Net-(D27-Pad1)") (class "Default")
      (node (ref "D27") (pin "1") (pinfunction "1_1") (pintype "passive"))
      (node (ref "R42") (pin "2") (pinfunction "2_2") (pintype "passive"))
      (node (ref "R43") (pin "1") (pinfunction "1_1") (pintype "passive"))
      (node (ref "S9") (pin "3") (pinfunction "3_3") (pintype "passive"))
    )
    (net (code "25") (name "Net-(D31-Pad1)") (class "Default")
      (node (ref "D31") (pin "1") (pinfunction "1_1") (pintype "passive"))
      (node (ref "R47") (pin "2") (pinfunction "2_2") (pintype "passive"))
      (node (ref "R48") (pin "1") (pinfunction "1_1") (pintype "passive"))
      (node (ref "S10") (pin "3") (pinfunction "3_3") (pintype "passive"))
    )
    (net (code "26") (name "Net-(D32-Pad1)") (class "Default")
      (node (ref "D32") (pin "1") (pinfunction "1_1") (pintype "passive"))
      (node (ref "R50") (pin "2") (pinfunction "2_2") (pintype "passive"))
      (node (ref "R52") (pin "1") (pinfunction "1_1") (pintype "passive"))
      (node (ref "S11") (pin "3") (pinfunction "3_3") (pintype "passive"))
    )
    (net (code "27") (name "Net-(J6-H)") (class "Default")
      (node (ref "D24") (pin "1") (pinfunction "1_1") (pintype "passive"))
      (node (ref "J6") (pin "H2") (pinfunction "H_H2") (pintype "passive"))
      (node (ref "R36") (pin "1") (pinfunction "1_1") (pintype "passive"))
    )
    (net (code "28") (name "Net-(J6-SEL+)") (class "Default")
      (node (ref "D25") (pin "1") (pinfunction "1_1") (pintype "passive"))
      (node (ref "J6") (pin "B1A") (pinfunction "SEL+_B1A") (pintype "passive"))
      (node (ref "R33") (pin "2") (pinfunction "2_2") (pintype "passive"))
      (node (ref "R35") (pin "1") (pinfunction "1_1") (pintype "passive"))
    )
    (net (code "29") (name "Net-(J6-V)") (class "Default")
      (node (ref "D23") (pin "1") (pinfunction "1_1") (pintype "passive"))
      (node (ref "J6") (pin "V2") (pinfunction "V_V2") (pintype "passive"))
      (node (ref "R39") (pin "1") (pinfunction "1_1") (pintype "passive"))
    )
    (net (code "30") (name "Net-(J7-H)") (class "Default")
      (node (ref "D29") (pin "1") (pinfunction "1_1") (pintype "passive"))
      (node (ref "J7") (pin "H2") (pinfunction "H_H2") (pintype "passive"))
      (node (ref "R45") (pin "1") (pinfunction "1_1") (pintype "passive"))
    )
    (net (code "31") (name "Net-(J7-SEL+)") (class "Default")
      (node (ref "D30") (pin "1") (pinfunction "1_1") (pintype "passive"))
      (node (ref "J7") (pin "B1A") (pinfunction "SEL+_B1A") (pintype "passive"))
      (node (ref "R41") (pin "2") (pinfunction "2_2") (pintype "passive"))
      (node (ref "R44") (pin "1") (pinfunction "1_1") (pintype "passive"))
    )
    (net (code "32") (name "Net-(J7-V)") (class "Default")
      (node (ref "D28") (pin "1") (pinfunction "1_1") (pintype "passive"))
      (node (ref "J7") (pin "V2") (pinfunction "V_V2") (pintype "passive"))
      (node (ref "R46") (pin "1") (pinfunction "1_1") (pintype "passive"))
    )
    (net (code "33") (name "Net-(J8-H)") (class "Default")
      (node (ref "D34") (pin "1") (pinfunction "1_1") (pintype "passive"))
      (node (ref "J8") (pin "H2") (pinfunction "H_H2") (pintype "passive"))
      (node (ref "R53") (pin "1") (pinfunction "1_1") (pintype "passive"))
    )
    (net (code "34") (name "Net-(J8-SEL+)") (class "Default")
      (node (ref "D35") (pin "1") (pinfunction "1_1") (pintype "passive"))
      (node (ref "J8") (pin "B1A") (pinfunction "SEL+_B1A") (pintype "passive"))
      (node (ref "R49") (pin "2") (pinfunction "2_2") (pintype "passive"))
      (node (ref "R51") (pin "1") (pinfunction "1_1") (pintype "passive"))
    )
    (net (code "35") (name "Net-(J8-V)") (class "Default")
      (node (ref "D33") (pin "1") (pinfunction "1_1") (pintype "passive"))
      (node (ref "J8") (pin "V2") (pinfunction "V_V2") (pintype "passive"))
      (node (ref "R54") (pin "1") (pinfunction "1_1") (pintype "passive"))
    )
    (net (code "36") (name "Net-(VR2-WIPER)") (class "Default")
      (node (ref "D26") (pin "1") (pinfunction "1_1") (pintype "passive"))
      (node (ref "R40") (pin "1") (pinfunction "1_1") (pintype "passive"))
      (node (ref "VR2") (pin "2") (pinfunction "WIPER_2") (pintype "passive"))
    )
    (net (code "37") (name "unconnected-(J6-SHIELD-PadS1)") (class "Default")
      (node (ref "J6") (pin "S1") (pinfunction "SHIELD_S1") (pintype "passive+no_connect"))
    )
    (net (code "38") (name "unconnected-(J6-SHIELD-PadS2)") (class "Default")
      (node (ref "J6") (pin "S2") (pinfunction "SHIELD_S2") (pintype "passive+no_connect"))
    )
    (net (code "39") (name "unconnected-(J6-SHIELD-PadS3)") (class "Default")
      (node (ref "J6") (pin "S3") (pinfunction "SHIELD_S3") (pintype "passive+no_connect"))
    )
    (net (code "40") (name "unconnected-(J6-SHIELD-PadS4)") (class "Default")
      (node (ref "J6") (pin "S4") (pinfunction "SHIELD_S4") (pintype "passive+no_connect"))
    )
    (net (code "41") (name "unconnected-(J7-SHIELD-PadS1)") (class "Default")
      (node (ref "J7") (pin "S1") (pinfunction "SHIELD_S1") (pintype "passive+no_connect"))
    )
    (net (code "42") (name "unconnected-(J7-SHIELD-PadS2)") (class "Default")
      (node (ref "J7") (pin "S2") (pinfunction "SHIELD_S2") (pintype "passive+no_connect"))
    )
    (net (code "43") (name "unconnected-(J7-SHIELD-PadS3)") (class "Default")
      (node (ref "J7") (pin "S3") (pinfunction "SHIELD_S3") (pintype "passive+no_connect"))
    )
    (net (code "44") (name "unconnected-(J7-SHIELD-PadS4)") (class "Default")
      (node (ref "J7") (pin "S4") (pinfunction "SHIELD_S4") (pintype "passive+no_connect"))
    )
    (net (code "45") (name "unconnected-(J8-SHIELD-PadS1)") (class "Default")
      (node (ref "J8") (pin "S1") (pinfunction "SHIELD_S1") (pintype "passive+no_connect"))
    )
    (net (code "46") (name "unconnected-(J8-SHIELD-PadS2)") (class "Default")
      (node (ref "J8") (pin "S2") (pinfunction "SHIELD_S2") (pintype "passive+no_connect"))
    )
    (net (code "47") (name "unconnected-(J8-SHIELD-PadS3)") (class "Default")
      (node (ref "J8") (pin "S3") (pinfunction "SHIELD_S3") (pintype "passive+no_connect"))
    )
    (net (code "48") (name "unconnected-(J8-SHIELD-PadS4)") (class "Default")
      (node (ref "J8") (pin "S4") (pinfunction "SHIELD_S4") (pintype "passive+no_connect"))
    )
    (net (code "49") (name "unconnected-(S6-Pad2)") (class "Default")
      (node (ref "S6") (pin "2") (pinfunction "2_2") (pintype "passive+no_connect"))
    )
    (net (code "50") (name "unconnected-(S6-Pad4)") (class "Default")
      (node (ref "S6") (pin "4") (pinfunction "4_4") (pintype "passive+no_connect"))
    )
    (net (code "51") (name "unconnected-(S8-Pad2)") (class "Default")
      (node (ref "S8") (pin "2") (pinfunction "2_2") (pintype "passive+no_connect"))
    )
    (net (code "52") (name "unconnected-(S8-Pad4)") (class "Default")
      (node (ref "S8") (pin "4") (pinfunction "4_4") (pintype "passive+no_connect"))
    )
    (net (code "53") (name "unconnected-(S9-Pad2)") (class "Default")
      (node (ref "S9") (pin "2") (pinfunction "2_2") (pintype "passive+no_connect"))
    )
    (net (code "54") (name "unconnected-(S9-Pad4)") (class "Default")
      (node (ref "S9") (pin "4") (pinfunction "4_4") (pintype "passive+no_connect"))
    )
    (net (code "55") (name "unconnected-(S10-Pad2)") (class "Default")
      (node (ref "S10") (pin "2") (pinfunction "2_2") (pintype "passive+no_connect"))
    )
    (net (code "56") (name "unconnected-(S10-Pad4)") (class "Default")
      (node (ref "S10") (pin "4") (pinfunction "4_4") (pintype "passive+no_connect"))
    )
    (net (code "57") (name "unconnected-(S11-Pad2)") (class "Default")
      (node (ref "S11") (pin "2") (pinfunction "2_2") (pintype "passive+no_connect"))
    )
    (net (code "58") (name "unconnected-(S11-Pad4)") (class "Default")
      (node (ref "S11") (pin "4") (pinfunction "4_4") (pintype "passive+no_connect"))
    )
    (net (code "59") (name "unconnected-(VR2-NC-Pad4)") (class "Default")
      (node (ref "VR2") (pin "4") (pinfunction "NC_4") (pintype "passive+no_connect"))
    )
    (net (code "60") (name "unconnected-(VR2-NC-Pad5)") (class "Default")
      (node (ref "VR2") (pin "5") (pinfunction "NC_5") (pintype "passive+no_connect"))
    )
    (net (code "61") (name "unconnected-(VR2-NC-Pad6)") (class "Default")
      (node (ref "VR2") (pin "6") (pinfunction "NC_6") (pintype "passive+no_connect"))
    )
    (net (code "62") (name "unconnected-(VR2-NC-Pad7)") (class "Default")
      (node (ref "VR2") (pin "7") (pinfunction "NC_7") (pintype "passive+no_connect"))
    )
  )
)
